# design.net
KiCad netlist of a schematic drawn in EasyEDA Pro
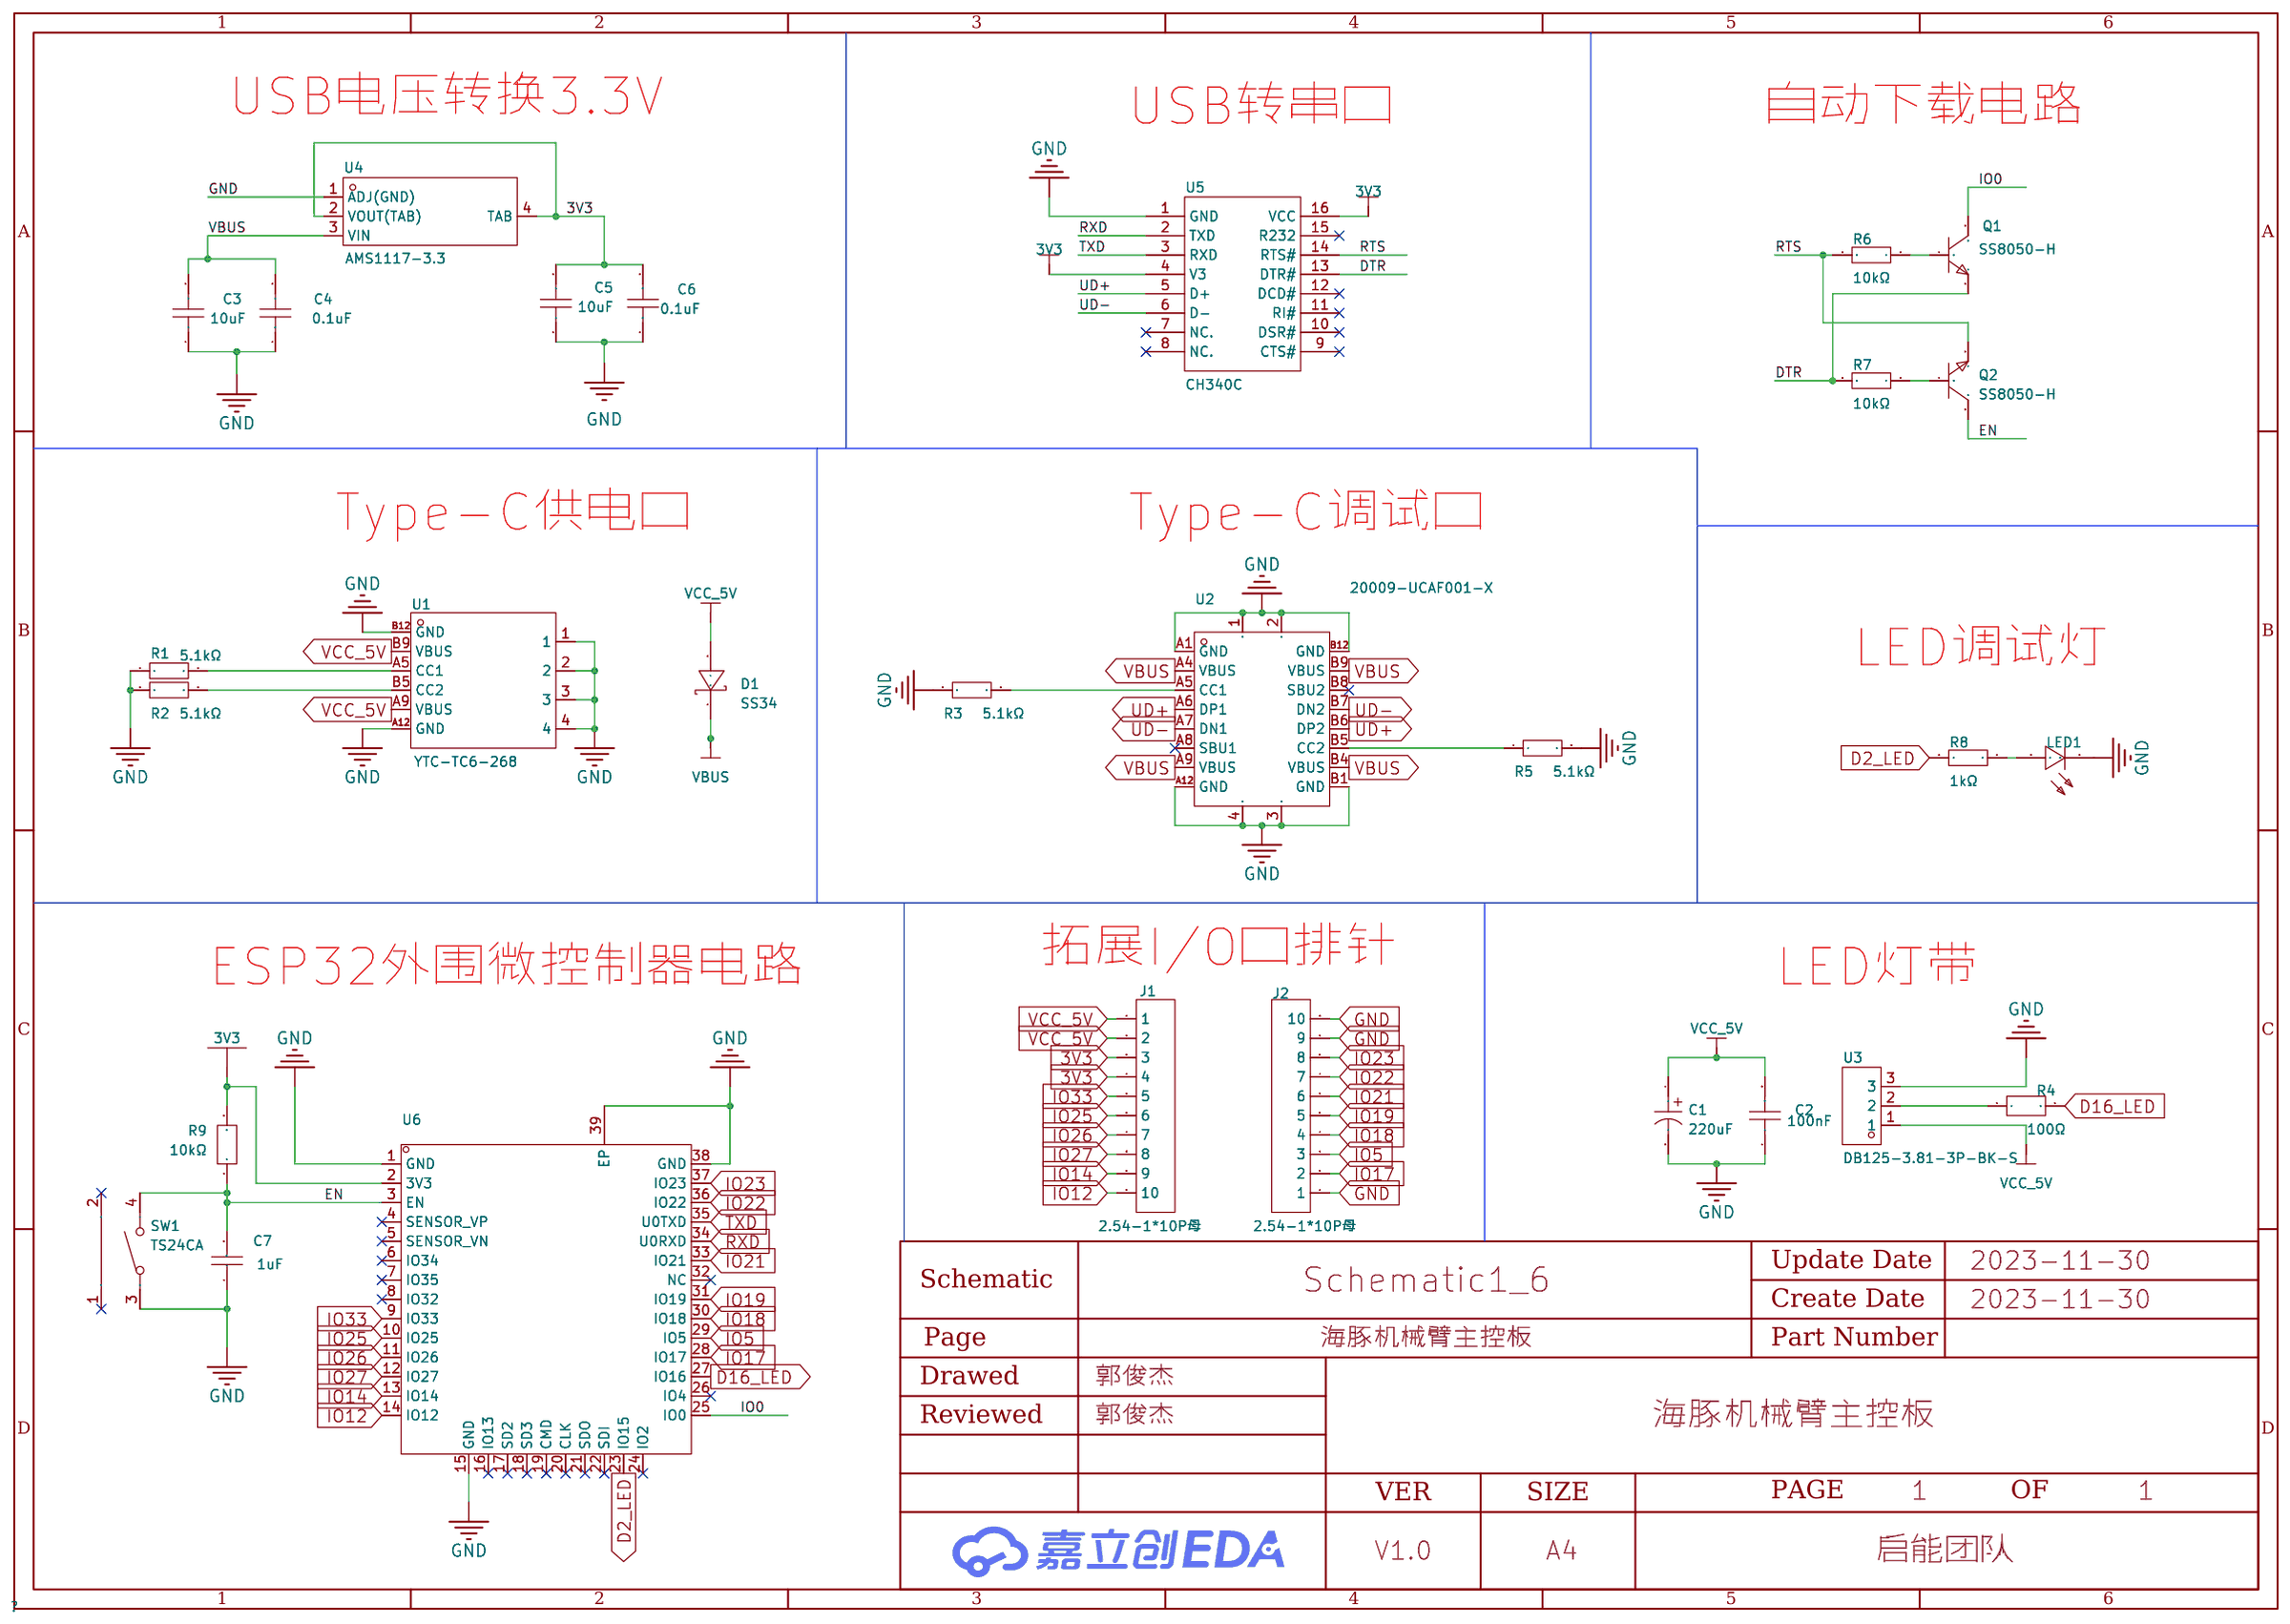
[diagram p0: schematic sheet]

(export (version "E")
  (design (tool "Eeschema 10.0.6"))
  (components
    (comp (ref "C1")
      (value "220uF")
      (footprint "easyedapro:CAP-SMD_BD6.3-L6.6-W6.6-FD-2")
      (description "容值:220uF;额定电压:16V;")
      (fields
        (field (name "Manufacturer Part") "RX220UF16V90RV0106")
        (field (name "Manufacturer") "KNSCHA(科尼盛)")
      )
      (libsource (lib "easyedapro") (part "RX220UF16V90RV0106"))
    )
    (comp (ref "C2")
      (value "100nF")
      (footprint "easyedapro:C0603")
      (description "容值:100nF;精度:±10%;额定电压:50V;材质(温度系数):X7R;")
      (fields
        (field (name "Manufacturer Part") "CL10B104KB8NNNC")
        (field (name "Manufacturer") "SAMSUNG(三星)")
      )
      (libsource (lib "easyedapro") (part "CL10B104KB8NNNC"))
    )
    (comp (ref "C3")
      (value "10uF")
      (footprint "easyedapro:c0603")
      (description "容值:10uF;精度:±0.25pF;额定电压:50V;温度系数:NP0;")
      (fields (field (name "Manufacturer Part") "MT18N1R5C500CT") (field (name "Manufacturer") "华新科(Walsin)"))
      (libsource (lib "easyedapro") (part "mt18n1r5c500ct"))
    )
    (comp (ref "C4")
      (value "0.1uF")
      (footprint "easyedapro:c0603")
      (description "容值：100nF 精度：±10% 额定电压：50V 材质(温度系数)：X7R 材质:X7R")
      (fields (field (name "Manufacturer Part") "MT18N1R5C500CT") (field (name "Manufacturer") "华新科(Walsin)"))
      (libsource (lib "easyedapro") (part "mt18n1r5c500ct"))
    )
    (comp (ref "C5")
      (value "10uF")
      (footprint "easyedapro:c0603")
      (description "容值:10uF;精度:±0.25pF;额定电压:50V;温度系数:NP0;")
      (fields (field (name "Manufacturer Part") "MT18N1R5C500CT") (field (name "Manufacturer") "华新科(Walsin)"))
      (libsource (lib "easyedapro") (part "mt18n1r5c500ct"))
    )
    (comp (ref "C6")
      (value "0.1uF")
      (footprint "easyedapro:c0603")
      (description "容值：100nF 精度：±10% 额定电压：50V 材质(温度系数)：X7R 材质:X7R")
      (fields (field (name "Manufacturer Part") "MT18N1R5C500CT") (field (name "Manufacturer") "华新科(Walsin)"))
      (libsource (lib "easyedapro") (part "mt18n1r5c500ct"))
    )
    (comp (ref "C7")
      (value "1uF")
      (footprint "easyedapro:C0603")
      (description "容值:1uF;精度:±10%;额定电压:50V;材质(温度系数):X5R;")
      (fields
        (field (name "Manufacturer Part") "CL10A105KB8NNNC")
        (field (name "Manufacturer") "SAMSUNG(三星)")
      )
      (libsource (lib "easyedapro") (part "CL10A105KB8NNNC"))
    )
    (comp (ref "D1")
      (value "SS34")
      (footprint "easyedapro:DO-214AC_L4.3-W2.7-LS5.3-RD")
      (description "二极管配置:独立式;直流反向耐压(Vr):40V;平均整流电流(Io):3A;正向压降(Vf):550mV@3A;反向电流(Ir):500uA@40V;")
      (fields (field (name "Manufacturer") "MDD"))
      (libsource (lib "easyedapro") (part "SS34_C8678"))
    )
    (comp (ref "J1")
      (value "2.54-1*10P母")
      (footprint "easyedapro:HDR-TH_10P-P2.54-V-F")
      (description "排数:单排;总孔位数:10;间距:2.54mm;插孔结构:1x10P;行距:-;安装类型:直插;塑高:-;触头材质:-;触头镀层:-;")
      (fields (field (name "Manufacturer") "BOOMELE(博穆精密)"))
      (libsource (lib "easyedapro") (part "Header-Female-2.54_1x10"))
    )
    (comp (ref "J2")
      (value "2.54-1*10P母")
      (footprint "easyedapro:HDR-TH_10P-P2.54-V-F")
      (description "排数:单排;总孔位数:10;间距:2.54mm;插孔结构:1x10P;行距:-;安装类型:直插;塑高:-;触头材质:-;触头镀层:-;")
      (fields (field (name "Manufacturer") "BOOMELE(博穆精密)"))
      (libsource (lib "easyedapro") (part "Header-Female-2.54_1x10"))
    )
    (comp (ref "LED1")
      (value "19-217/GHC-YR1S2/3T")
      (footprint "easyedapro:LED0603-RD")
      (fields (field (name "Manufacturer") "EVERLIGHT(亿光)"))
      (libsource (lib "easyedapro") (part "19-217/GHC-YR1S2/3T"))
    )
    (comp (ref "Q1")
      (value "SS8050-H")
      (footprint "easyedapro:SOT-23-3_L2.9-W1.3-P1.90-LS2.4-BR")
      (fields (field (name "Manufacturer") "YANGJIE(扬杰)"))
      (libsource (lib "easyedapro") (part "SS8050-H"))
    )
    (comp (ref "Q2")
      (value "SS8050-H")
      (footprint "easyedapro:SOT-23-3_L2.9-W1.3-P1.90-LS2.4-BR")
      (fields (field (name "Manufacturer") "YANGJIE(扬杰)"))
      (libsource (lib "easyedapro") (part "SS8050-H"))
    )
    (comp (ref "R1")
      (value "5.1kΩ")
      (footprint "easyedapro:R0603")
      (description "电阻类型:厚膜电阻;阻值:5.1kΩ;精度:±1%;功率:100mW;温度系数:±100ppm/;最大工作电压:75V;工作温度范围:-55~+155;")
      (fields
        (field (name "Manufacturer Part") "0603WAF5101T5E")
        (field (name "Manufacturer") "UNI-ROYAL(厚声)")
      )
      (libsource (lib "easyedapro") (part "0603WAF5101T5E"))
    )
    (comp (ref "R2")
      (value "5.1kΩ")
      (footprint "easyedapro:R0603")
      (description "电阻类型:厚膜电阻;阻值:5.1kΩ;精度:±1%;功率:100mW;温度系数:±100ppm/;最大工作电压:75V;工作温度范围:-55~+155;")
      (fields
        (field (name "Manufacturer Part") "0603WAF5101T5E")
        (field (name "Manufacturer") "UNI-ROYAL(厚声)")
      )
      (libsource (lib "easyedapro") (part "0603WAF5101T5E"))
    )
    (comp (ref "R3")
      (value "5.1kΩ")
      (footprint "easyedapro:R0603")
      (description "电阻类型:厚膜电阻;阻值:5.1kΩ;精度:±1%;功率:100mW;温度系数:±100ppm/;最大工作电压:75V;工作温度范围:-55~+155;")
      (fields
        (field (name "Manufacturer Part") "0603WAF5101T5E")
        (field (name "Manufacturer") "UNI-ROYAL(厚声)")
      )
      (libsource (lib "easyedapro") (part "0603WAF5101T5E"))
    )
    (comp (ref "R4")
      (value "100Ω")
      (footprint "easyedapro:R0603")
      (description "电阻类型:厚膜电阻;阻值:100Ω;精度:±5%;功率:100mW;温度系数:±100ppm/;最大工作电压:75V;工作温度范围:-55~+155;")
      (fields (field (name "Manufacturer Part") "0603 ±5% 100Ω") (field (name "Manufacturer") "VO(翔胜)"))
      (libsource (lib "easyedapro") (part "0603 ±5% 100Ω"))
    )
    (comp (ref "R5")
      (value "5.1kΩ")
      (footprint "easyedapro:R0603")
      (description "电阻类型:厚膜电阻;阻值:5.1kΩ;精度:±1%;功率:100mW;温度系数:±100ppm/;最大工作电压:75V;工作温度范围:-55~+155;")
      (fields
        (field (name "Manufacturer Part") "0603WAF5101T5E")
        (field (name "Manufacturer") "UNI-ROYAL(厚声)")
      )
      (libsource (lib "easyedapro") (part "0603WAF5101T5E"))
    )
    (comp (ref "R6")
      (value "10kΩ")
      (footprint "easyedapro:R0603")
      (description "阻值:10kΩ;精度:±1%;功率:100mW;温度系数:±100ppm/;最大工作电压:-;工作温度范围:-55~+155;")
      (fields (field (name "Manufacturer Part") "ERJ3EKF1002V") (field (name "Manufacturer") "PANASONIC(松下)"))
      (libsource (lib "easyedapro") (part "ERJ-3EKF1002V"))
    )
    (comp (ref "R7")
      (value "10kΩ")
      (footprint "easyedapro:R0603")
      (description "阻值:10kΩ;精度:±1%;功率:100mW;温度系数:±100ppm/;最大工作电压:-;工作温度范围:-55~+155;")
      (fields (field (name "Manufacturer Part") "ERJ3EKF1002V") (field (name "Manufacturer") "PANASONIC(松下)"))
      (libsource (lib "easyedapro") (part "ERJ-3EKF1002V"))
    )
    (comp (ref "R8")
      (value "1kΩ")
      (footprint "easyedapro:R0603")
      (description "电阻类型:厚膜电阻;阻值:1kΩ;精度:±1%;功率:100mW;温度系数:±100ppm/;最大工作电压:75V;工作温度范围:-55~+155;")
      (fields
        (field (name "Manufacturer Part") "0603WAF1001T5E")
        (field (name "Manufacturer") "UNI-ROYAL(厚声)")
      )
      (libsource (lib "easyedapro") (part "0603WAF1001T5E"))
    )
    (comp (ref "R9")
      (value "10kΩ")
      (footprint "easyedapro:r0603")
      (description "阻值:10kΩ;精度:±1%;功率:-;温度系数:-;")
      (fields (field (name "Manufacturer Part") "SG73P1JTTD1002F") (field (name "Manufacturer") "KOA"))
      (libsource (lib "easyedapro") (part "sg73p1jttd1002f"))
    )
    (comp (ref "SW1")
      (value "TS24CA")
      (footprint "easyedapro:SW-SMD_TS24CA")
      (description "触点电流:50mA;额定电压(DC):12V;电路结构:单刀单掷;安装方式:卧贴;按钮形状:矩形按钮;带灯:-;开关长度:4.55mm;开关宽度:1.8mm;开关高度:3.5mm;")
      (fields (field (name "Manufacturer") "SHOU HAN(首韩)"))
      (libsource (lib "easyedapro") (part "TS24CA"))
    )
    (comp (ref "U1")
      (value "YTC-TC6-268")
      (footprint "easyedapro:TYPE-C-SMD_YIYUAN_YTC-TC6-268")
      (description "连接器类型:Type-C;公母:母座;触点数量:6;")
      (fields (field (name "Manufacturer") "YIYUAN(怡远)"))
      (libsource (lib "easyedapro") (part "YTC-TC6-268"))
    )
    (comp (ref "U2")
      (value "20009-UCAF001-X")
      (footprint "easyedapro:TYPE-C-SMD_20009-UCAF001-X")
      (fields (field (name "Manufacturer") "MINTRON(明硕)"))
      (libsource (lib "easyedapro") (part "20009-UCAF001-X"))
    )
    (comp (ref "U3")
      (value "DB125-3.81-3P-BK-S")
      (footprint "easyedapro:CONN-TH_DB125-3.81-3P-BK")
      (fields (field (name "Manufacturer") "DIBO(地博电气)"))
      (libsource (lib "easyedapro") (part "DB125-3.81-3P-BK"))
    )
    (comp (ref "U4")
      (value "AMS1117-3.3")
      (footprint "easyedapro:SOT-223-4_L6.5-W3.5-P2.30-LS7.0-BR")
      (description "输出类型:固定;输出极性:正;输出通道数:1;最大输入电压:18V;输出电压:3.3V;压差:1.3V@(1A);输出电流:1A;电源纹波抑制比(PSRR):60dB@(120Hz);")
      (fields (field (name "Manufacturer") "UMW(广东友台半导体)"))
      (libsource (lib "easyedapro") (part "AMS1117-3.3_C347222"))
    )
    (comp (ref "U5")
      (value "CH340C")
      (footprint "easyedapro:SOP-16_L10.0-W3.9-P1.27-LS6.0-BL")
      (description "类型:Transceiver;协议类别:USB 2.0;驱动器/接收器数:-;数据速率:2Mbps;")
      (fields (field (name "Manufacturer") "WCH(南京沁恒)"))
      (libsource (lib "easyedapro") (part "CH340C"))
    )
    (comp (ref "U6")
      (value "~")
      (footprint "easyedapro:wirelm-smd_esp32-s")
      (fields (field (name "Manufacturer Part") "ESP32-S") (field (name "Manufacturer") "Ai-Thinker(安信可)"))
      (libsource (lib "easyedapro") (part "esp32-s"))
    )
  )
  (nets
    (net (code "1") (name "/DTR") (class "Default")
      (node (ref "Q1") (pin "2") (pinfunction "E_2") (pintype "input"))
      (node (ref "R7") (pin "2") (pinfunction "2_2") (pintype "input"))
      (node (ref "U5") (pin "13") (pinfunction "DTR#_13") (pintype "input"))
    )
    (net (code "2") (name "/EN") (class "Default")
      (node (ref "C7") (pin "2") (pinfunction "2_2") (pintype "input"))
      (node (ref "Q2") (pin "3") (pinfunction "C_3") (pintype "input"))
      (node (ref "R9") (pin "1") (pinfunction "1_1") (pintype "input"))
      (node (ref "SW1") (pin "4") (pinfunction "4_4") (pintype "input"))
      (node (ref "U6") (pin "3") (pinfunction "EN_3") (pintype "input"))
    )
    (net (code "3") (name "/IO0") (class "Default")
      (node (ref "Q1") (pin "3") (pinfunction "C_3") (pintype "input"))
      (node (ref "U6") (pin "25") (pinfunction "IO0_25") (pintype "input"))
    )
    (net (code "4") (name "/RTS") (class "Default")
      (node (ref "Q2") (pin "2") (pinfunction "E_2") (pintype "input"))
      (node (ref "R6") (pin "2") (pinfunction "2_2") (pintype "input"))
      (node (ref "U5") (pin "14") (pinfunction "RTS#_14") (pintype "input"))
    )
    (net (code "5") (name "3V3") (class "Default")
      (node (ref "C5") (pin "2") (pinfunction "2_2") (pintype "input"))
      (node (ref "C6") (pin "2") (pinfunction "2_2") (pintype "input"))
      (node (ref "J1") (pin "3") (pinfunction "3_3") (pintype "input"))
      (node (ref "J1") (pin "4") (pinfunction "4_4") (pintype "input"))
      (node (ref "R9") (pin "2") (pinfunction "2_2") (pintype "input"))
      (node (ref "U4") (pin "2") (pinfunction "VOUT(TAB)_2") (pintype "input"))
      (node (ref "U4") (pin "4") (pinfunction "TAB_4") (pintype "input"))
      (node (ref "U5") (pin "16") (pinfunction "VCC_16") (pintype "input"))
      (node (ref "U5") (pin "4") (pinfunction "V3_4") (pintype "input"))
      (node (ref "U6") (pin "2") (pinfunction "3V3_2") (pintype "input"))
    )
    (net (code "6") (name "D2_LED") (class "Default")
      (node (ref "R8") (pin "2") (pinfunction "2_2") (pintype "input"))
      (node (ref "U6") (pin "23") (pinfunction "IO15_23") (pintype "input"))
    )
    (net (code "7") (name "D16_LED") (class "Default")
      (node (ref "R4") (pin "2") (pinfunction "2_2") (pintype "input"))
      (node (ref "U6") (pin "27") (pinfunction "IO16_27") (pintype "input"))
    )
    (net (code "8") (name "GND") (class "Default")
      (node (ref "C1") (pin "2") (pinfunction "2_2") (pintype "input"))
      (node (ref "C2") (pin "1") (pinfunction "1_1") (pintype "input"))
      (node (ref "C3") (pin "1") (pinfunction "1_1") (pintype "input"))
      (node (ref "C4") (pin "1") (pinfunction "1_1") (pintype "input"))
      (node (ref "C5") (pin "1") (pinfunction "1_1") (pintype "input"))
      (node (ref "C6") (pin "1") (pinfunction "1_1") (pintype "input"))
      (node (ref "C7") (pin "1") (pinfunction "1_1") (pintype "input"))
      (node (ref "J2") (pin "1") (pinfunction "1_1") (pintype "input"))
      (node (ref "J2") (pin "10") (pinfunction "10_10") (pintype "input"))
      (node (ref "J2") (pin "9") (pinfunction "9_9") (pintype "input"))
      (node (ref "LED1") (pin "1") (pinfunction "C_1") (pintype "input"))
      (node (ref "R1") (pin "1") (pinfunction "1_1") (pintype "input"))
      (node (ref "R2") (pin "1") (pinfunction "1_1") (pintype "input"))
      (node (ref "R3") (pin "1") (pinfunction "1_1") (pintype "input"))
      (node (ref "R5") (pin "2") (pinfunction "2_2") (pintype "input"))
      (node (ref "SW1") (pin "3") (pinfunction "3_3") (pintype "input"))
      (node (ref "U1") (pin "1") (pinfunction "1_1") (pintype "input"))
      (node (ref "U1") (pin "2") (pinfunction "2_2") (pintype "input"))
      (node (ref "U1") (pin "3") (pinfunction "3_3") (pintype "input"))
      (node (ref "U1") (pin "4") (pinfunction "4_4") (pintype "input"))
      (node (ref "U1") (pin "A12") (pinfunction "GND_A12") (pintype "input"))
      (node (ref "U1") (pin "B12") (pinfunction "GND_B12") (pintype "input"))
      (node (ref "U2") (pin "1") (pinfunction "1_1") (pintype "input"))
      (node (ref "U2") (pin "2") (pinfunction "2_2") (pintype "input"))
      (node (ref "U2") (pin "3") (pinfunction "3_3") (pintype "input"))
      (node (ref "U2") (pin "4") (pinfunction "4_4") (pintype "input"))
      (node (ref "U2") (pin "A1") (pinfunction "GND_A1") (pintype "input"))
      (node (ref "U2") (pin "A12") (pinfunction "GND_A12") (pintype "input"))
      (node (ref "U2") (pin "B1") (pinfunction "GND_B1") (pintype "input"))
      (node (ref "U2") (pin "B12") (pinfunction "GND_B12") (pintype "input"))
      (node (ref "U3") (pin "3") (pinfunction "3_3") (pintype "input"))
      (node (ref "U4") (pin "1") (pinfunction "ADJ(GND)_1") (pintype "input"))
      (node (ref "U5") (pin "1") (pinfunction "GND_1") (pintype "input"))
      (node (ref "U6") (pin "1") (pinfunction "GND_1") (pintype "input"))
      (node (ref "U6") (pin "15") (pinfunction "GND_15") (pintype "input"))
      (node (ref "U6") (pin "38") (pinfunction "GND_38") (pintype "input"))
      (node (ref "U6") (pin "39") (pinfunction "EP_39") (pintype "input"))
    )
    (net (code "9") (name "IO5") (class "Default")
      (node (ref "J2") (pin "3") (pinfunction "3_3") (pintype "input"))
      (node (ref "U6") (pin "29") (pinfunction "IO5_29") (pintype "input"))
    )
    (net (code "10") (name "IO12") (class "Default")
      (node (ref "J1") (pin "10") (pinfunction "10_10") (pintype "input"))
      (node (ref "U6") (pin "14") (pinfunction "IO12_14") (pintype "input"))
    )
    (net (code "11") (name "IO14") (class "Default")
      (node (ref "J1") (pin "9") (pinfunction "9_9") (pintype "input"))
      (node (ref "U6") (pin "13") (pinfunction "IO14_13") (pintype "input"))
    )
    (net (code "12") (name "IO17") (class "Default")
      (node (ref "J2") (pin "2") (pinfunction "2_2") (pintype "input"))
      (node (ref "U6") (pin "28") (pinfunction "IO17_28") (pintype "input"))
    )
    (net (code "13") (name "IO18") (class "Default")
      (node (ref "J2") (pin "4") (pinfunction "4_4") (pintype "input"))
      (node (ref "U6") (pin "30") (pinfunction "IO18_30") (pintype "input"))
    )
    (net (code "14") (name "IO19") (class "Default")
      (node (ref "J2") (pin "5") (pinfunction "5_5") (pintype "input"))
      (node (ref "U6") (pin "31") (pinfunction "IO19_31") (pintype "input"))
    )
    (net (code "15") (name "IO21") (class "Default")
      (node (ref "J2") (pin "6") (pinfunction "6_6") (pintype "input"))
      (node (ref "U6") (pin "33") (pinfunction "IO21_33") (pintype "input"))
    )
    (net (code "16") (name "IO22") (class "Default")
      (node (ref "J2") (pin "7") (pinfunction "7_7") (pintype "input"))
      (node (ref "U6") (pin "36") (pinfunction "IO22_36") (pintype "input"))
    )
    (net (code "17") (name "IO23") (class "Default")
      (node (ref "J2") (pin "8") (pinfunction "8_8") (pintype "input"))
      (node (ref "U6") (pin "37") (pinfunction "IO23_37") (pintype "input"))
    )
    (net (code "18") (name "IO25") (class "Default")
      (node (ref "J1") (pin "6") (pinfunction "6_6") (pintype "input"))
      (node (ref "U6") (pin "10") (pinfunction "IO25_10") (pintype "input"))
    )
    (net (code "19") (name "IO26") (class "Default")
      (node (ref "J1") (pin "7") (pinfunction "7_7") (pintype "input"))
      (node (ref "U6") (pin "11") (pinfunction "IO26_11") (pintype "input"))
    )
    (net (code "20") (name "IO27") (class "Default")
      (node (ref "J1") (pin "8") (pinfunction "8_8") (pintype "input"))
      (node (ref "U6") (pin "12") (pinfunction "IO27_12") (pintype "input"))
    )
    (net (code "21") (name "IO33") (class "Default")
      (node (ref "J1") (pin "5") (pinfunction "5_5") (pintype "input"))
      (node (ref "U6") (pin "9") (pinfunction "IO33_9") (pintype "input"))
    )
    (net (code "22") (name "Net-(LED1-A)") (class "Default")
      (node (ref "LED1") (pin "2") (pinfunction "A_2") (pintype "input"))
      (node (ref "R8") (pin "1") (pinfunction "1_1") (pintype "input"))
    )
    (net (code "23") (name "Net-(Q1-B)") (class "Default")
      (node (ref "Q1") (pin "1") (pinfunction "B_1") (pintype "input"))
      (node (ref "R6") (pin "1") (pinfunction "1_1") (pintype "input"))
    )
    (net (code "24") (name "Net-(Q2-B)") (class "Default")
      (node (ref "Q2") (pin "1") (pinfunction "B_1") (pintype "input"))
      (node (ref "R7") (pin "1") (pinfunction "1_1") (pintype "input"))
    )
    (net (code "25") (name "Net-(R4-Pad1)") (class "Default")
      (node (ref "R4") (pin "1") (pinfunction "1_1") (pintype "input"))
      (node (ref "U3") (pin "2") (pinfunction "2_2") (pintype "input"))
    )
    (net (code "26") (name "Net-(U1-CC1)") (class "Default")
      (node (ref "R1") (pin "2") (pinfunction "2_2") (pintype "input"))
      (node (ref "U1") (pin "A5") (pinfunction "CC1_A5") (pintype "input"))
    )
    (net (code "27") (name "Net-(U1-CC2)") (class "Default")
      (node (ref "R2") (pin "2") (pinfunction "2_2") (pintype "input"))
      (node (ref "U1") (pin "B5") (pinfunction "CC2_B5") (pintype "input"))
    )
    (net (code "28") (name "Net-(U2-CC1)") (class "Default")
      (node (ref "R3") (pin "2") (pinfunction "2_2") (pintype "input"))
      (node (ref "U2") (pin "A5") (pinfunction "CC1_A5") (pintype "input"))
    )
    (net (code "29") (name "Net-(U2-CC2)") (class "Default")
      (node (ref "R5") (pin "1") (pinfunction "1_1") (pintype "input"))
      (node (ref "U2") (pin "B5") (pinfunction "CC2_B5") (pintype "input"))
    )
    (net (code "30") (name "RXD") (class "Default")
      (node (ref "U5") (pin "2") (pinfunction "TXD_2") (pintype "input"))
      (node (ref "U6") (pin "34") (pinfunction "U0RXD_34") (pintype "input"))
    )
    (net (code "31") (name "TXD") (class "Default")
      (node (ref "U5") (pin "3") (pinfunction "RXD_3") (pintype "input"))
      (node (ref "U6") (pin "35") (pinfunction "U0TXD_35") (pintype "input"))
    )
    (net (code "32") (name "UD+") (class "Default")
      (node (ref "U2") (pin "A6") (pinfunction "DP1_A6") (pintype "input"))
      (node (ref "U2") (pin "B6") (pinfunction "DP2_B6") (pintype "input"))
      (node (ref "U5") (pin "5") (pinfunction "D+_5") (pintype "input"))
    )
    (net (code "33") (name "UD-") (class "Default")
      (node (ref "U2") (pin "A7") (pinfunction "DN1_A7") (pintype "input"))
      (node (ref "U2") (pin "B7") (pinfunction "DN2_B7") (pintype "input"))
      (node (ref "U5") (pin "6") (pinfunction "D-_6") (pintype "input"))
    )
    (net (code "34") (name "VBUS") (class "Default")
      (node (ref "C3") (pin "2") (pinfunction "2_2") (pintype "input"))
      (node (ref "C4") (pin "2") (pinfunction "2_2") (pintype "input"))
      (node (ref "D1") (pin "1") (pinfunction "K_1") (pintype "input"))
      (node (ref "U2") (pin "A4") (pinfunction "VBUS_A4") (pintype "input"))
      (node (ref "U2") (pin "A9") (pinfunction "VBUS_A9") (pintype "input"))
      (node (ref "U2") (pin "B4") (pinfunction "VBUS_B4") (pintype "input"))
      (node (ref "U2") (pin "B9") (pinfunction "VBUS_B9") (pintype "input"))
      (node (ref "U4") (pin "3") (pinfunction "VIN_3") (pintype "input"))
    )
    (net (code "35") (name "VCC_5V") (class "Default")
      (node (ref "C1") (pin "1") (pinfunction "1_1") (pintype "input"))
      (node (ref "C2") (pin "2") (pinfunction "2_2") (pintype "input"))
      (node (ref "D1") (pin "2") (pinfunction "A_2") (pintype "input"))
      (node (ref "J1") (pin "1") (pinfunction "1_1") (pintype "input"))
      (node (ref "J1") (pin "2") (pinfunction "2_2") (pintype "input"))
      (node (ref "U1") (pin "A9") (pinfunction "VBUS_A9") (pintype "input"))
      (node (ref "U1") (pin "B9") (pinfunction "VBUS_B9") (pintype "input"))
      (node (ref "U3") (pin "1") (pinfunction "1_1") (pintype "input"))
    )
    (net (code "36") (name "unconnected-(SW1-Pad1)") (class "Default")
      (node (ref "SW1") (pin "1") (pinfunction "1_1") (pintype "input+no_connect"))
    )
    (net (code "37") (name "unconnected-(SW1-Pad2)") (class "Default")
      (node (ref "SW1") (pin "2") (pinfunction "2_2") (pintype "input+no_connect"))
    )
    (net (code "38") (name "unconnected-(U2-SBU1-PadA8)") (class "Default")
      (node (ref "U2") (pin "A8") (pinfunction "SBU1_A8") (pintype "input+no_connect"))
    )
    (net (code "39") (name "unconnected-(U2-SBU2-PadB8)") (class "Default")
      (node (ref "U2") (pin "B8") (pinfunction "SBU2_B8") (pintype "input+no_connect"))
    )
    (net (code "40") (name "unconnected-(U5-CTS#-Pad9)") (class "Default")
      (node (ref "U5") (pin "9") (pinfunction "CTS#_9") (pintype "input+no_connect"))
    )
    (net (code "41") (name "unconnected-(U5-DCD#-Pad12)") (class "Default")
      (node (ref "U5") (pin "12") (pinfunction "DCD#_12") (pintype "input+no_connect"))
    )
    (net (code "42") (name "unconnected-(U5-DSR#-Pad10)") (class "Default")
      (node (ref "U5") (pin "10") (pinfunction "DSR#_10") (pintype "input+no_connect"))
    )
    (net (code "43") (name "unconnected-(U5-NC.-Pad7)") (class "Default")
      (node (ref "U5") (pin "7") (pinfunction "NC._7") (pintype "input+no_connect"))
    )
    (net (code "44") (name "unconnected-(U5-NC.-Pad8)") (class "Default")
      (node (ref "U5") (pin "8") (pinfunction "NC._8") (pintype "input+no_connect"))
    )
    (net (code "45") (name "unconnected-(U5-R232-Pad15)") (class "Default")
      (node (ref "U5") (pin "15") (pinfunction "R232_15") (pintype "input+no_connect"))
    )
    (net (code "46") (name "unconnected-(U5-RI#-Pad11)") (class "Default")
      (node (ref "U5") (pin "11") (pinfunction "RI#_11") (pintype "input+no_connect"))
    )
    (net (code "47") (name "unconnected-(U6-CLK-Pad20)") (class "Default")
      (node (ref "U6") (pin "20") (pinfunction "CLK_20") (pintype "input+no_connect"))
    )
    (net (code "48") (name "unconnected-(U6-CMD-Pad19)") (class "Default")
      (node (ref "U6") (pin "19") (pinfunction "CMD_19") (pintype "input+no_connect"))
    )
    (net (code "49") (name "unconnected-(U6-IO2-Pad24)") (class "Default")
      (node (ref "U6") (pin "24") (pinfunction "IO2_24") (pintype "input+no_connect"))
    )
    (net (code "50") (name "unconnected-(U6-IO4-Pad26)") (class "Default")
      (node (ref "U6") (pin "26") (pinfunction "IO4_26") (pintype "input+no_connect"))
    )
    (net (code "51") (name "unconnected-(U6-IO13-Pad16)") (class "Default")
      (node (ref "U6") (pin "16") (pinfunction "IO13_16") (pintype "input+no_connect"))
    )
    (net (code "52") (name "unconnected-(U6-IO32-Pad8)") (class "Default")
      (node (ref "U6") (pin "8") (pinfunction "IO32_8") (pintype "input+no_connect"))
    )
    (net (code "53") (name "unconnected-(U6-IO34-Pad6)") (class "Default")
      (node (ref "U6") (pin "6") (pinfunction "IO34_6") (pintype "input+no_connect"))
    )
    (net (code "54") (name "unconnected-(U6-IO35-Pad7)") (class "Default")
      (node (ref "U6") (pin "7") (pinfunction "IO35_7") (pintype "input+no_connect"))
    )
    (net (code "55") (name "unconnected-(U6-NC-Pad32)") (class "Default")
      (node (ref "U6") (pin "32") (pinfunction "NC_32") (pintype "input+no_connect"))
    )
    (net (code "56") (name "unconnected-(U6-SD2-Pad17)") (class "Default")
      (node (ref "U6") (pin "17") (pinfunction "SD2_17") (pintype "input+no_connect"))
    )
    (net (code "57") (name "unconnected-(U6-SD3-Pad18)") (class "Default")
      (node (ref "U6") (pin "18") (pinfunction "SD3_18") (pintype "input+no_connect"))
    )
    (net (code "58") (name "unconnected-(U6-SDI-Pad22)") (class "Default")
      (node (ref "U6") (pin "22") (pinfunction "SDI_22") (pintype "input+no_connect"))
    )
    (net (code "59") (name "unconnected-(U6-SDO-Pad21)") (class "Default")
      (node (ref "U6") (pin "21") (pinfunction "SDO_21") (pintype "input+no_connect"))
    )
    (net (code "60") (name "unconnected-(U6-SENSOR_VN-Pad5)") (class "Default")
      (node (ref "U6") (pin "5") (pinfunction "SENSOR_VN_5") (pintype "input+no_connect"))
    )
    (net (code "61") (name "unconnected-(U6-SENSOR_VP-Pad4)") (class "Default")
      (node (ref "U6") (pin "4") (pinfunction "SENSOR_VP_4") (pintype "input+no_connect"))
    )
  )
)
